# TCRT5000-w-LDR.net
KiCad netlist of a schematic drawn in EasyEDA
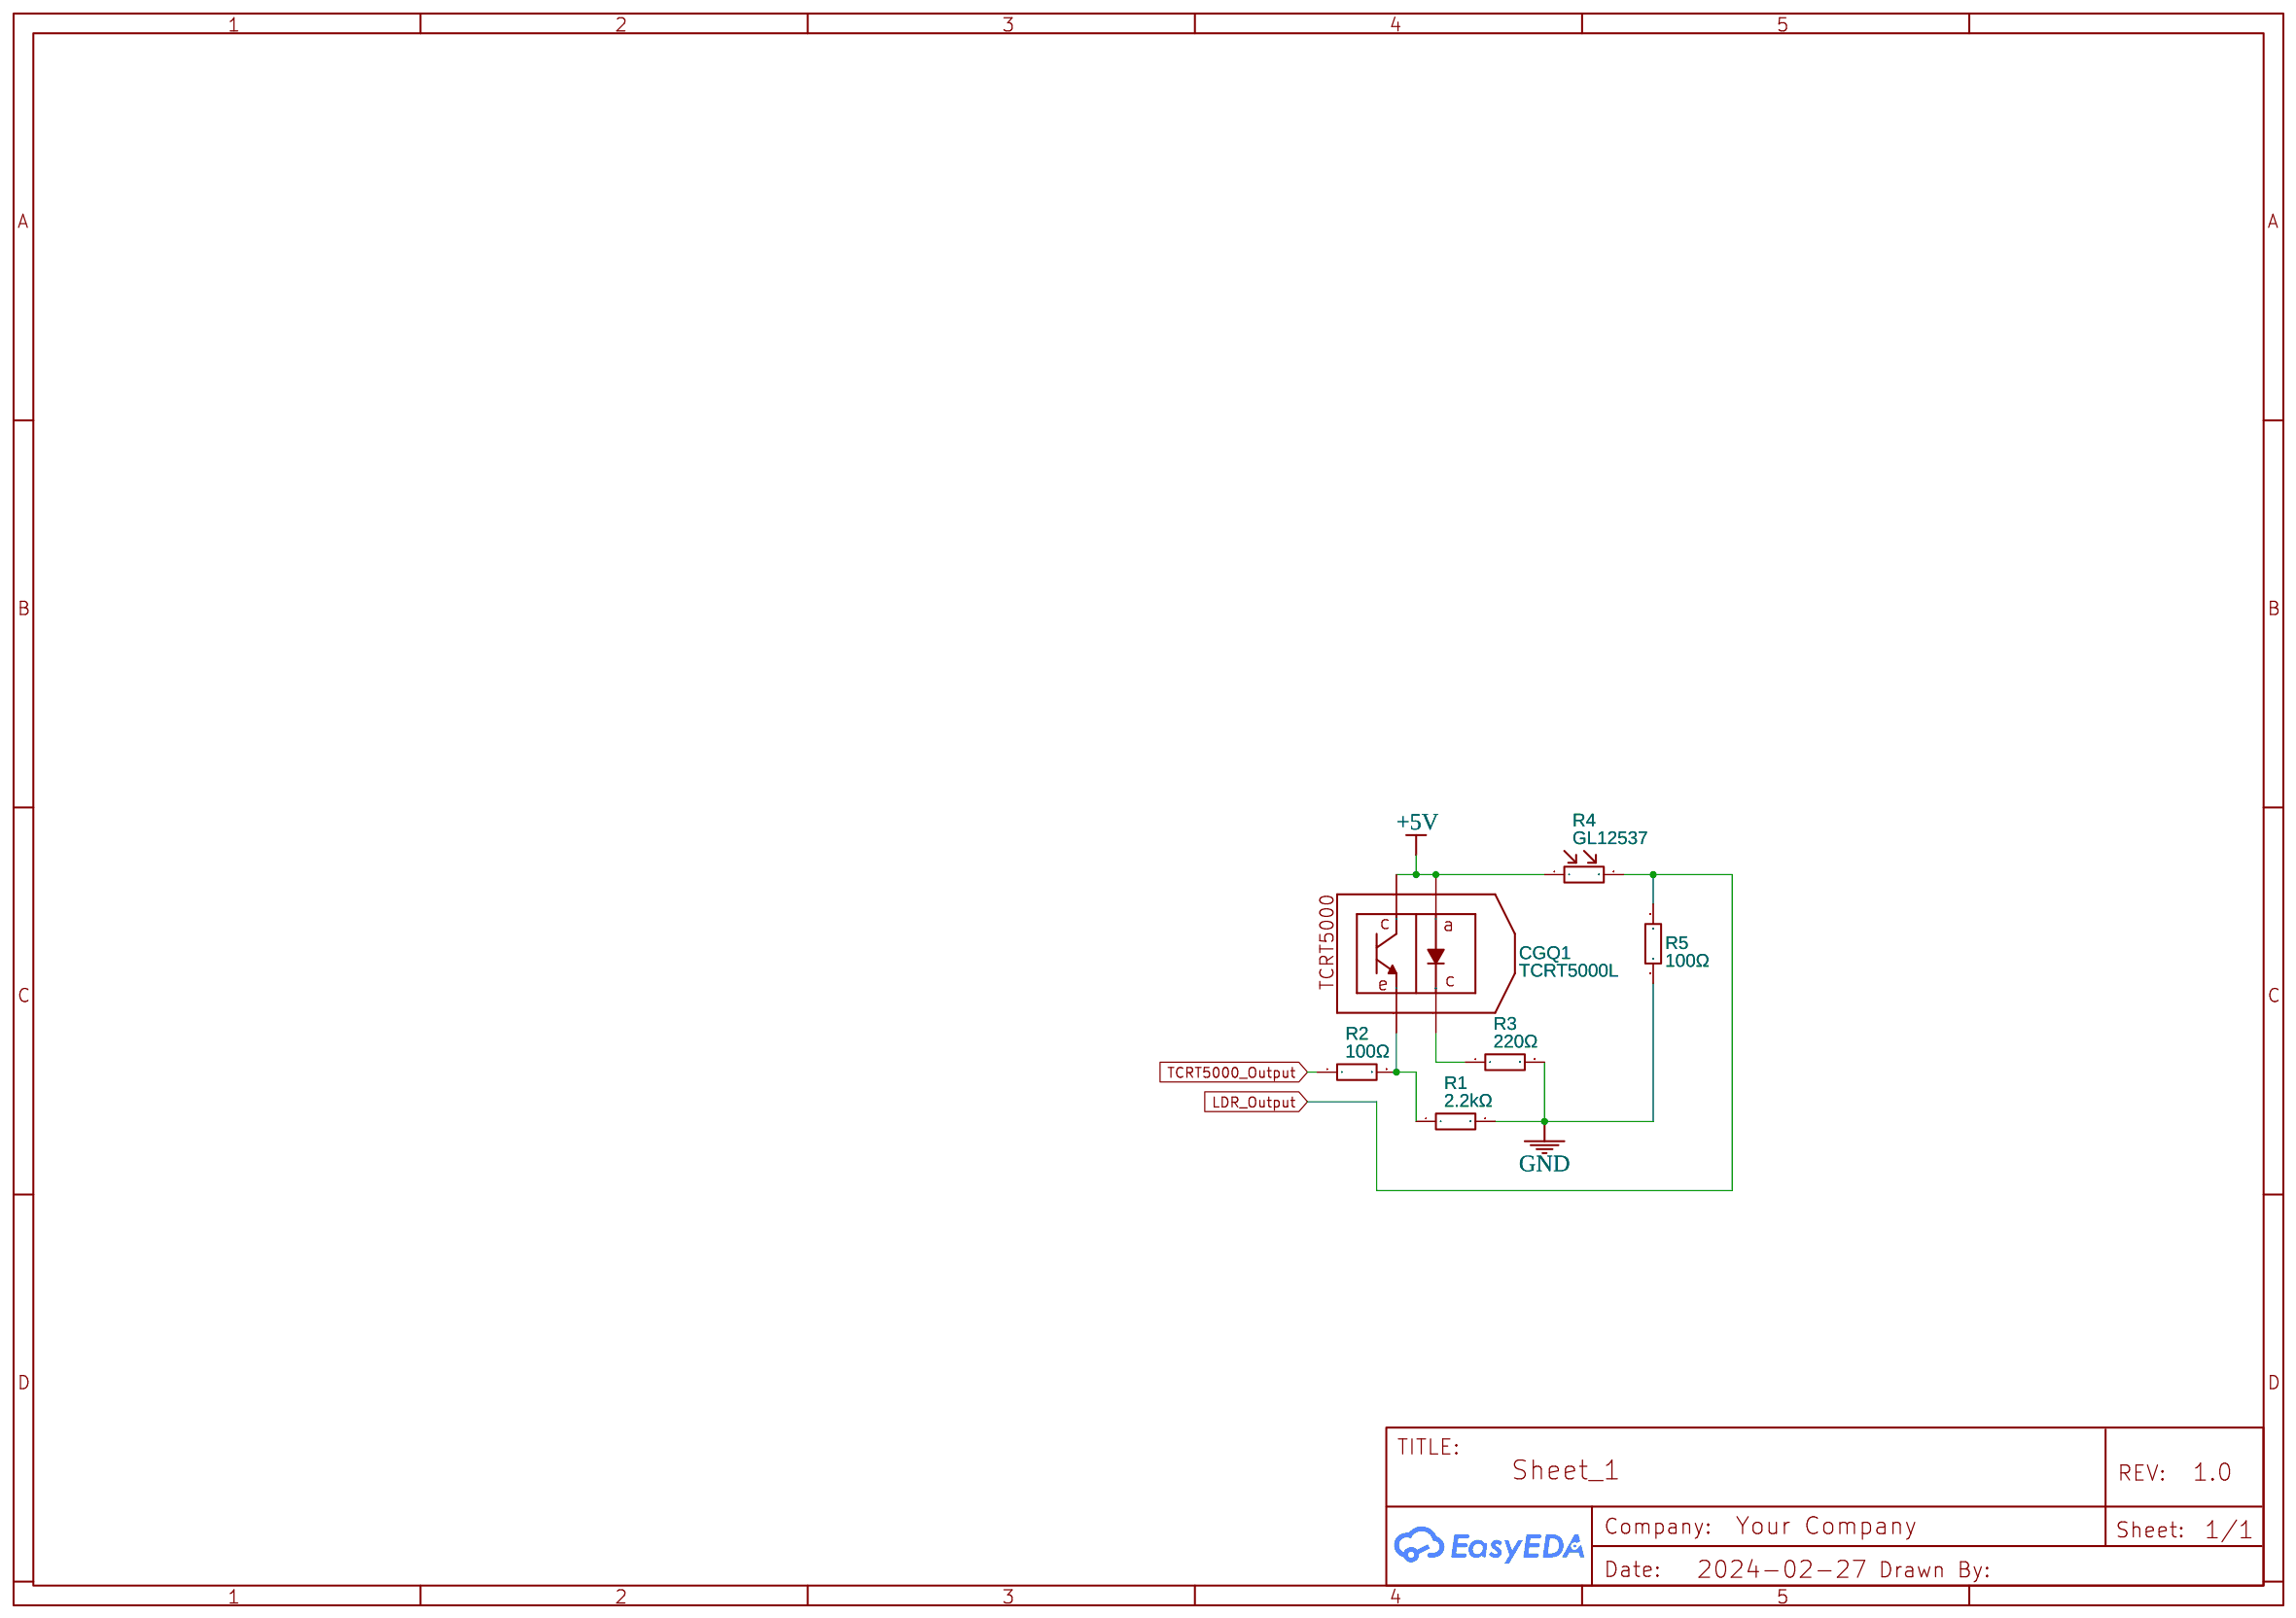
[diagram p0: schematic sheet]

(export (version "E")
  (design (tool "Eeschema 10.0.6"))
  (components
    (comp (ref "CGQ1")
      (value "TCRT5000L")
      (fields (field (name "Manufacturer") "VISHAY(威世)"))
      (libsource (lib "") (part "TCRT5000L"))
    )
    (comp (ref "R1")
      (value "2.2kΩ")
      (fields
        (field (name "Manufacturer Part") "CFR0W4J0222A50")
        (field (name "Manufacturer") "UNI-ROYAL(厚声)")
      )
      (libsource (lib "") (part "CFR0W4J0222A50"))
    )
    (comp (ref "R2")
      (value "100Ω")
      (fields (field (name "Manufacturer Part") "CF1/4W-100Ω±5% T") (field (name "Manufacturer") "CCO(千志电子)"))
      (libsource (lib "") (part "CF1/4W-100Ω±5% T52"))
    )
    (comp (ref "R3")
      (value "220Ω")
      (fields (field (name "Manufacturer Part") "CF1/4W-220Ω±5% T") (field (name "Manufacturer") "CCO(千志电子)"))
      (libsource (lib "") (part "CF1/4W-220Ω±5% T52"))
    )
    (comp (ref "R4")
      (value "GL12537")
      (fields (field (name "Manufacturer") "JCHL(晶创和立)"))
      (libsource (lib "") (part "GL12537"))
    )
    (comp (ref "R5")
      (value "100Ω")
      (fields (field (name "Manufacturer Part") "CF1/4W-100Ω±5% T") (field (name "Manufacturer") "CCO(千志电子)"))
      (libsource (lib "") (part "CF1/4W-100Ω±5% T52_1"))
    )
  )
  (nets
    (net (code "1") (name "+5V") (class "Default")
      (node (ref "CGQ1") (pin "1") (pinfunction "C_1") (pintype "unspecified"))
      (node (ref "CGQ1") (pin "3") (pinfunction "A_3") (pintype "unspecified"))
      (node (ref "R4") (pin "1") (pinfunction "1_1") (pintype "input"))
    )
    (net (code "2") (name "GND") (class "Default")
      (node (ref "R1") (pin "2") (pinfunction "2_2") (pintype "input"))
      (node (ref "R3") (pin "2") (pinfunction "2_2") (pintype "unspecified"))
      (node (ref "R5") (pin "1") (pinfunction "1_1") (pintype "unspecified"))
    )
    (net (code "3") (name "LDR_Output") (class "Default")
      (node (ref "R4") (pin "2") (pinfunction "2_2") (pintype "input"))
      (node (ref "R5") (pin "2") (pinfunction "2_2") (pintype "unspecified"))
    )
    (net (code "4") (name "Net-(CGQ1-C-Pad4)") (class "Default")
      (node (ref "CGQ1") (pin "4") (pinfunction "C_4") (pintype "unspecified"))
      (node (ref "R3") (pin "1") (pinfunction "1_1") (pintype "unspecified"))
    )
    (net (code "5") (name "Net-(CGQ1-E)") (class "Default")
      (node (ref "CGQ1") (pin "2") (pinfunction "E_2") (pintype "unspecified"))
      (node (ref "R1") (pin "1") (pinfunction "1_1") (pintype "input"))
      (node (ref "R2") (pin "2") (pinfunction "2_2") (pintype "unspecified"))
    )
    (net (code "6") (name "TCRT5000_Output") (class "Default")
      (node (ref "R2") (pin "1") (pinfunction "1_1") (pintype "unspecified"))
    )
  )
)
